# norbi_lm_single_power_ch.net
KiCad netlist of a schematic drawn in Altium Designer
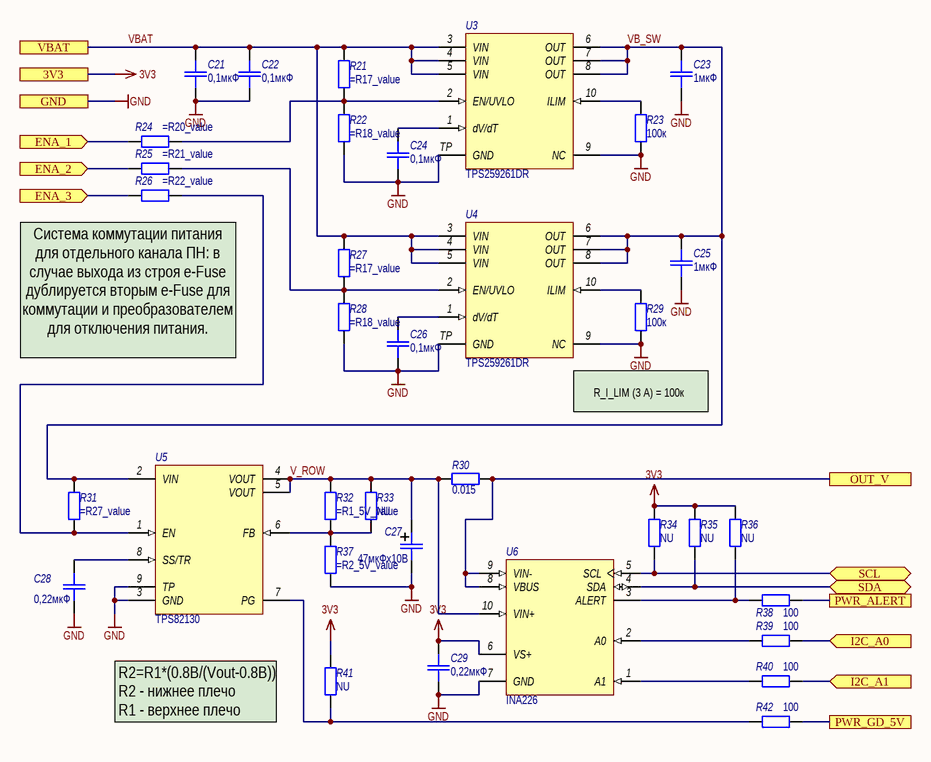
[diagram p0: norbi_lm_single_power_ch.SchDoc]

(export (version "E")
  (design (tool "Eeschema 10.0.6"))
  (components
    (comp (ref "C21")
      (value "0,1мкФ")
      (footprint "CR-0603")
      (description "Конденсатор для поверхностного монтажа")
      (libsource (lib "my_passive") (part "C_smd"))
    )
    (comp (ref "C22")
      (value "0,1мкФ")
      (footprint "CR-0603")
      (description "Конденсатор для поверхностного монтажа")
      (libsource (lib "my_passive") (part "C_smd"))
    )
    (comp (ref "C23")
      (value "1мкФ")
      (footprint "CR-0603")
      (description "Конденсатор для поверхностного монтажа")
      (libsource (lib "my_passive") (part "C_smd"))
    )
    (comp (ref "C24")
      (value "0,1мкФ")
      (footprint "CR-0603")
      (description "Конденсатор для поверхностного монтажа")
      (libsource (lib "my_passive") (part "C_smd"))
    )
    (comp (ref "C25")
      (value "1мкФ")
      (footprint "CR-0603")
      (description "Конденсатор для поверхностного монтажа")
      (libsource (lib "my_passive") (part "C_smd"))
    )
    (comp (ref "C26")
      (value "0,1мкФ")
      (footprint "CR-0603")
      (description "Конденсатор для поверхностного монтажа")
      (libsource (lib "my_passive") (part "C_smd"))
    )
    (comp (ref "C27")
      (value "47мкФх10В")
      (footprint "C_SMD_SIZE_B")
      (description "Поляризованный конеднсатор для поверхностного монтажа")
      (libsource (lib "my_passive") (part "C_pol_smd"))
    )
    (comp (ref "C28")
      (value "0,22мкФ")
      (footprint "CR-0603")
      (description "Конденсатор для поверхностного монтажа")
      (libsource (lib "my_passive") (part "C_smd"))
    )
    (comp (ref "C29")
      (value "0,22мкФ")
      (footprint "CR-0603")
      (description "Конденсатор для поверхностного монтажа")
      (libsource (lib "my_passive") (part "C_smd"))
    )
    (comp (ref "R21")
      (value "R17_value")
      (footprint "CR-0603")
      (description "Резистор для поверхностного монтажа")
      (libsource (lib "") (part "R_smd_2"))
    )
    (comp (ref "R22")
      (value "R18_value")
      (footprint "CR-0603")
      (description "Резистор для поверхностного монтажа")
      (libsource (lib "") (part "R_smd_2"))
    )
    (comp (ref "R23")
      (value "100к")
      (footprint "CR-0603")
      (description "Резистор для поверхностного монтажа")
      (libsource (lib "my_passive") (part "R_smd"))
    )
    (comp (ref "R24")
      (value "~")
      (footprint "CR-0603")
      (description "Резистор для поверхностного монтажа")
      (libsource (lib "") (part "R_smd_1"))
    )
    (comp (ref "R25")
      (value "~")
      (footprint "CR-0603")
      (description "Резистор для поверхностного монтажа")
      (libsource (lib "") (part "R_smd_1"))
    )
    (comp (ref "R26")
      (value "~")
      (footprint "CR-0603")
      (description "Резистор для поверхностного монтажа")
      (libsource (lib "") (part "R_smd_1"))
    )
    (comp (ref "R27")
      (value "R17_value")
      (footprint "CR-0603")
      (description "Резистор для поверхностного монтажа")
      (libsource (lib "") (part "R_smd_2"))
    )
    (comp (ref "R28")
      (value "R18_value")
      (footprint "CR-0603")
      (description "Резистор для поверхностного монтажа")
      (libsource (lib "") (part "R_smd_2"))
    )
    (comp (ref "R29")
      (value "100к")
      (footprint "CR-0603")
      (description "Резистор для поверхностного монтажа")
      (libsource (lib "my_passive") (part "R_smd"))
    )
    (comp (ref "R30")
      (value "0.015")
      (footprint "CR-1206")
      (description "Резистор для поверхностного монтажа")
      (fields (field (name "Comment") "0,01"))
      (libsource (lib "") (part "R_smd_1"))
    )
    (comp (ref "R31")
      (value "~")
      (footprint "CR-0603")
      (description "Резистор для поверхностного монтажа")
      (libsource (lib "my_passive") (part "R_smd"))
    )
    (comp (ref "R32")
      (value "~")
      (footprint "CR-0603")
      (description "Резистор для поверхностного монтажа")
      (libsource (lib "my_passive") (part "R_smd"))
    )
    (comp (ref "R33")
      (value "NU")
      (footprint "CR-0603")
      (description "Резистор для поверхностного монтажа")
      (libsource (lib "my_passive") (part "R_smd"))
    )
    (comp (ref "R34")
      (value "NU")
      (footprint "CR-0603")
      (description "Резистор для поверхностного монтажа")
      (libsource (lib "my_passive") (part "R_smd"))
    )
    (comp (ref "R35")
      (value "NU")
      (footprint "CR-0603")
      (description "Резистор для поверхностного монтажа")
      (libsource (lib "my_passive") (part "R_smd"))
    )
    (comp (ref "R36")
      (value "NU")
      (footprint "CR-0603")
      (description "Резистор для поверхностного монтажа")
      (libsource (lib "my_passive") (part "R_smd"))
    )
    (comp (ref "R37")
      (value "~")
      (footprint "CR-0603")
      (description "Резистор для поверхностного монтажа")
      (libsource (lib "my_passive") (part "R_smd"))
    )
    (comp (ref "R38")
      (value "100")
      (footprint "CR-0603")
      (description "Резистор для поверхностного монтажа")
      (libsource (lib "") (part "R_smd_1"))
    )
    (comp (ref "R39")
      (value "100")
      (footprint "CR-0603")
      (description "Резистор для поверхностного монтажа")
      (libsource (lib "") (part "R_smd_1"))
    )
    (comp (ref "R40")
      (value "100")
      (footprint "CR-0603")
      (description "Резистор для поверхностного монтажа")
      (libsource (lib "") (part "R_smd_1"))
    )
    (comp (ref "R41")
      (value "NU")
      (footprint "CR-0603")
      (description "Резистор для поверхностного монтажа")
      (libsource (lib "my_passive") (part "R_smd"))
    )
    (comp (ref "R42")
      (value "100")
      (footprint "CR-0603")
      (description "Резистор для поверхностного монтажа")
      (libsource (lib "") (part "R_smd_1"))
    )
    (comp (ref "U3")
      (value "TPS259261ВК")
      (footprint "VSON-10")
      (description "Simple 5-V/12-V eFuse Protection Switches")
      (fields (field (name "НАИМЕНОВАНИЕ") "TPS259261DR"))
      (libsource (lib "my_power") (part "TPS259261"))
    )
    (comp (ref "U4")
      (value "TPS259261ВК")
      (footprint "VSON-10")
      (description "Simple 5-V/12-V eFuse Protection Switches")
      (fields (field (name "НАИМЕНОВАНИЕ") "TPS259261DR"))
      (libsource (lib "my_power") (part "TPS259261"))
    )
    (comp (ref "U5")
      (value "TPS82130")
      (footprint "uSiL-8")
      (description "17-V Input 3-A Step-Down Converter MicroSiP™ Module with Integrated Inductor")
      (fields (field (name "НАИМЕНОВАНИЕ") "TPS82130"))
      (libsource (lib "my_power") (part "TPS82130"))
    )
    (comp (ref "U6")
      (value "INA226")
      (footprint "VSSOP-8")
      (description "High- or Low-Side Measurement, Bidirectional Current and Power Monitor With I2C Interface")
      (fields (field (name "НАИМЕНОВАНИЕ") "INA226"))
      (libsource (lib "my_power") (part "INA226"))
    )
  )
  (nets
    (net (code "1") (name "/ENA_1") (class "Default")
      (node (ref "R24") (pin "2") (pinfunction "2_2") (pintype "passive"))
    )
    (net (code "2") (name "/ENA_2") (class "Default")
      (node (ref "R25") (pin "2") (pinfunction "2_2") (pintype "passive"))
    )
    (net (code "3") (name "/ENA_3") (class "Default")
      (node (ref "R26") (pin "2") (pinfunction "2_2") (pintype "passive"))
    )
    (net (code "4") (name "/I2C_A0") (class "Default")
      (node (ref "R39") (pin "1") (pinfunction "1_1") (pintype "passive"))
    )
    (net (code "5") (name "/I2C_A1") (class "Default")
      (node (ref "R40") (pin "1") (pinfunction "1_1") (pintype "passive"))
    )
    (net (code "6") (name "/OUT_V") (class "Default")
      (node (ref "R30") (pin "1") (pinfunction "1_1") (pintype "passive"))
      (node (ref "U6") (pin "8") (pinfunction "VBUS_8") (pintype "input"))
      (node (ref "U6") (pin "9") (pinfunction "VIN-_9") (pintype "input"))
    )
    (net (code "7") (name "/PWR_ALERT") (class "Default")
      (node (ref "R38") (pin "1") (pinfunction "1_1") (pintype "passive"))
    )
    (net (code "8") (name "/PWR_GD_5V") (class "Default")
      (node (ref "R42") (pin "1") (pinfunction "1_1") (pintype "passive"))
    )
    (net (code "9") (name "/SCL") (class "Default")
      (node (ref "R34") (pin "1") (pinfunction "1_1") (pintype "passive"))
      (node (ref "U6") (pin "5") (pinfunction "SCL_5") (pintype "input"))
    )
    (net (code "10") (name "/SDA") (class "Default")
      (node (ref "R35") (pin "1") (pinfunction "1_1") (pintype "passive"))
      (node (ref "U6") (pin "4") (pinfunction "SDA_4") (pintype "bidirectional"))
    )
    (net (code "11") (name "/VBAT") (class "Default")
      (node (ref "C21") (pin "2") (pinfunction "2_2") (pintype "passive"))
      (node (ref "C22") (pin "2") (pinfunction "2_2") (pintype "passive"))
      (node (ref "R21") (pin "1") (pinfunction "1_1") (pintype "passive"))
      (node (ref "R27") (pin "1") (pinfunction "1_1") (pintype "passive"))
      (node (ref "U3") (pin "3") (pinfunction "VIN_3") (pintype "power_in"))
      (node (ref "U3") (pin "4") (pinfunction "VIN_4") (pintype "power_in"))
      (node (ref "U3") (pin "5") (pinfunction "VIN_5") (pintype "power_in"))
      (node (ref "U4") (pin "3") (pinfunction "VIN_3") (pintype "power_in"))
      (node (ref "U4") (pin "4") (pinfunction "VIN_4") (pintype "power_in"))
      (node (ref "U4") (pin "5") (pinfunction "VIN_5") (pintype "power_in"))
    )
    (net (code "12") (name "/VB_SW") (class "Default")
      (node (ref "C23") (pin "2") (pinfunction "2_2") (pintype "passive"))
      (node (ref "C25") (pin "2") (pinfunction "2_2") (pintype "passive"))
      (node (ref "R31") (pin "2") (pinfunction "2_2") (pintype "passive"))
      (node (ref "U3") (pin "6") (pinfunction "OUT_6") (pintype "power_in"))
      (node (ref "U3") (pin "7") (pinfunction "OUT_7") (pintype "power_in"))
      (node (ref "U3") (pin "8") (pinfunction "OUT_8") (pintype "power_in"))
      (node (ref "U4") (pin "6") (pinfunction "OUT_6") (pintype "power_in"))
      (node (ref "U4") (pin "7") (pinfunction "OUT_7") (pintype "power_in"))
      (node (ref "U4") (pin "8") (pinfunction "OUT_8") (pintype "power_in"))
      (node (ref "U5") (pin "2") (pinfunction "VIN_2") (pintype "power_in"))
    )
    (net (code "13") (name "/V_ROW") (class "Default")
      (node (ref "C27") (pin "1") (pinfunction "1_1") (pintype "passive"))
      (node (ref "R30") (pin "2") (pinfunction "2_2") (pintype "passive"))
      (node (ref "R32") (pin "2") (pinfunction "2_2") (pintype "passive"))
      (node (ref "R33") (pin "2") (pinfunction "2_2") (pintype "passive"))
      (node (ref "U5") (pin "4") (pinfunction "VOUT_4") (pintype "power_in"))
      (node (ref "U5") (pin "5") (pinfunction "VOUT_5") (pintype "power_in"))
      (node (ref "U6") (pin "10") (pinfunction "VIN+_10") (pintype "input"))
    )
    (net (code "14") (name "3V3") (class "Default")
      (node (ref "C29") (pin "2") (pinfunction "2_2") (pintype "passive"))
      (node (ref "R34") (pin "2") (pinfunction "2_2") (pintype "passive"))
      (node (ref "R35") (pin "2") (pinfunction "2_2") (pintype "passive"))
      (node (ref "R36") (pin "2") (pinfunction "2_2") (pintype "passive"))
      (node (ref "R41") (pin "2") (pinfunction "2_2") (pintype "passive"))
      (node (ref "U6") (pin "6") (pinfunction "VS+_6") (pintype "power_in"))
    )
    (net (code "15") (name "GND") (class "Default")
      (node (ref "C21") (pin "1") (pinfunction "1_1") (pintype "passive"))
      (node (ref "C22") (pin "1") (pinfunction "1_1") (pintype "passive"))
      (node (ref "C23") (pin "1") (pinfunction "1_1") (pintype "passive"))
      (node (ref "C24") (pin "1") (pinfunction "1_1") (pintype "passive"))
      (node (ref "C25") (pin "1") (pinfunction "1_1") (pintype "passive"))
      (node (ref "C26") (pin "1") (pinfunction "1_1") (pintype "passive"))
      (node (ref "C27") (pin "2") (pinfunction "2_2") (pintype "passive"))
      (node (ref "C28") (pin "1") (pinfunction "1_1") (pintype "passive"))
      (node (ref "C29") (pin "1") (pinfunction "1_1") (pintype "passive"))
      (node (ref "R22") (pin "2") (pinfunction "2_2") (pintype "passive"))
      (node (ref "R23") (pin "1") (pinfunction "1_1") (pintype "passive"))
      (node (ref "R28") (pin "2") (pinfunction "2_2") (pintype "passive"))
      (node (ref "R29") (pin "1") (pinfunction "1_1") (pintype "passive"))
      (node (ref "R37") (pin "1") (pinfunction "1_1") (pintype "passive"))
      (node (ref "U3") (pin "9") (pinfunction "NC_9") (pintype "passive"))
      (node (ref "U3") (pin "TP") (pinfunction "GND_TP") (pintype "power_in"))
      (node (ref "U4") (pin "9") (pinfunction "NC_9") (pintype "passive"))
      (node (ref "U4") (pin "TP") (pinfunction "GND_TP") (pintype "power_in"))
      (node (ref "U5") (pin "3") (pinfunction "GND_3") (pintype "power_in"))
      (node (ref "U5") (pin "9") (pinfunction "TP_9") (pintype "power_in"))
      (node (ref "U6") (pin "7") (pinfunction "GND_7") (pintype "power_in"))
    )
    (net (code "16") (name "Net-(U3-EN{slash}UVLO)") (class "Default")
      (node (ref "R21") (pin "2") (pinfunction "2_2") (pintype "passive"))
      (node (ref "R22") (pin "1") (pinfunction "1_1") (pintype "passive"))
      (node (ref "R24") (pin "1") (pinfunction "1_1") (pintype "passive"))
      (node (ref "U3") (pin "2") (pinfunction "EN/UVLO_2") (pintype "input"))
    )
    (net (code "17") (name "Net-(U3-ILIM)") (class "Default")
      (node (ref "R23") (pin "2") (pinfunction "2_2") (pintype "passive"))
      (node (ref "U3") (pin "10") (pinfunction "ILIM_10") (pintype "input"))
    )
    (net (code "18") (name "Net-(U3-dV{slash}dT)") (class "Default")
      (node (ref "C24") (pin "2") (pinfunction "2_2") (pintype "passive"))
      (node (ref "U3") (pin "1") (pinfunction "dV/dT_1") (pintype "input"))
    )
    (net (code "19") (name "Net-(U4-EN{slash}UVLO)") (class "Default")
      (node (ref "R25") (pin "1") (pinfunction "1_1") (pintype "passive"))
      (node (ref "R27") (pin "2") (pinfunction "2_2") (pintype "passive"))
      (node (ref "R28") (pin "1") (pinfunction "1_1") (pintype "passive"))
      (node (ref "U4") (pin "2") (pinfunction "EN/UVLO_2") (pintype "input"))
    )
    (net (code "20") (name "Net-(U4-ILIM)") (class "Default")
      (node (ref "R29") (pin "2") (pinfunction "2_2") (pintype "passive"))
      (node (ref "U4") (pin "10") (pinfunction "ILIM_10") (pintype "input"))
    )
    (net (code "21") (name "Net-(U4-dV{slash}dT)") (class "Default")
      (node (ref "C26") (pin "2") (pinfunction "2_2") (pintype "passive"))
      (node (ref "U4") (pin "1") (pinfunction "dV/dT_1") (pintype "input"))
    )
    (net (code "22") (name "Net-(U5-EN)") (class "Default")
      (node (ref "R26") (pin "1") (pinfunction "1_1") (pintype "passive"))
      (node (ref "R31") (pin "1") (pinfunction "1_1") (pintype "passive"))
      (node (ref "U5") (pin "1") (pinfunction "EN_1") (pintype "input"))
    )
    (net (code "23") (name "Net-(U5-FB)") (class "Default")
      (node (ref "R32") (pin "1") (pinfunction "1_1") (pintype "passive"))
      (node (ref "R33") (pin "1") (pinfunction "1_1") (pintype "passive"))
      (node (ref "R37") (pin "2") (pinfunction "2_2") (pintype "passive"))
      (node (ref "U5") (pin "6") (pinfunction "FB_6") (pintype "input"))
    )
    (net (code "24") (name "Net-(U5-PG)") (class "Default")
      (node (ref "R41") (pin "1") (pinfunction "1_1") (pintype "passive"))
      (node (ref "R42") (pin "2") (pinfunction "2_2") (pintype "passive"))
      (node (ref "U5") (pin "7") (pinfunction "PG_7") (pintype "open_collector"))
    )
    (net (code "25") (name "Net-(U5-SS{slash}TR)") (class "Default")
      (node (ref "C28") (pin "2") (pinfunction "2_2") (pintype "passive"))
      (node (ref "U5") (pin "8") (pinfunction "SS/TR_8") (pintype "input"))
    )
    (net (code "26") (name "Net-(U6-A0)") (class "Default")
      (node (ref "R39") (pin "2") (pinfunction "2_2") (pintype "passive"))
      (node (ref "U6") (pin "2") (pinfunction "A0_2") (pintype "input"))
    )
    (net (code "27") (name "Net-(U6-A1)") (class "Default")
      (node (ref "R40") (pin "2") (pinfunction "2_2") (pintype "passive"))
      (node (ref "U6") (pin "1") (pinfunction "A1_1") (pintype "input"))
    )
    (net (code "28") (name "Net-(U6-ALERT)") (class "Default")
      (node (ref "R36") (pin "1") (pinfunction "1_1") (pintype "passive"))
      (node (ref "R38") (pin "2") (pinfunction "2_2") (pintype "passive"))
      (node (ref "U6") (pin "3") (pinfunction "ALERT_3") (pintype "open_collector"))
    )
  )
)
